# AirU_v2_0_wADC.net
KiCad netlist of a schematic drawn in EAGLE
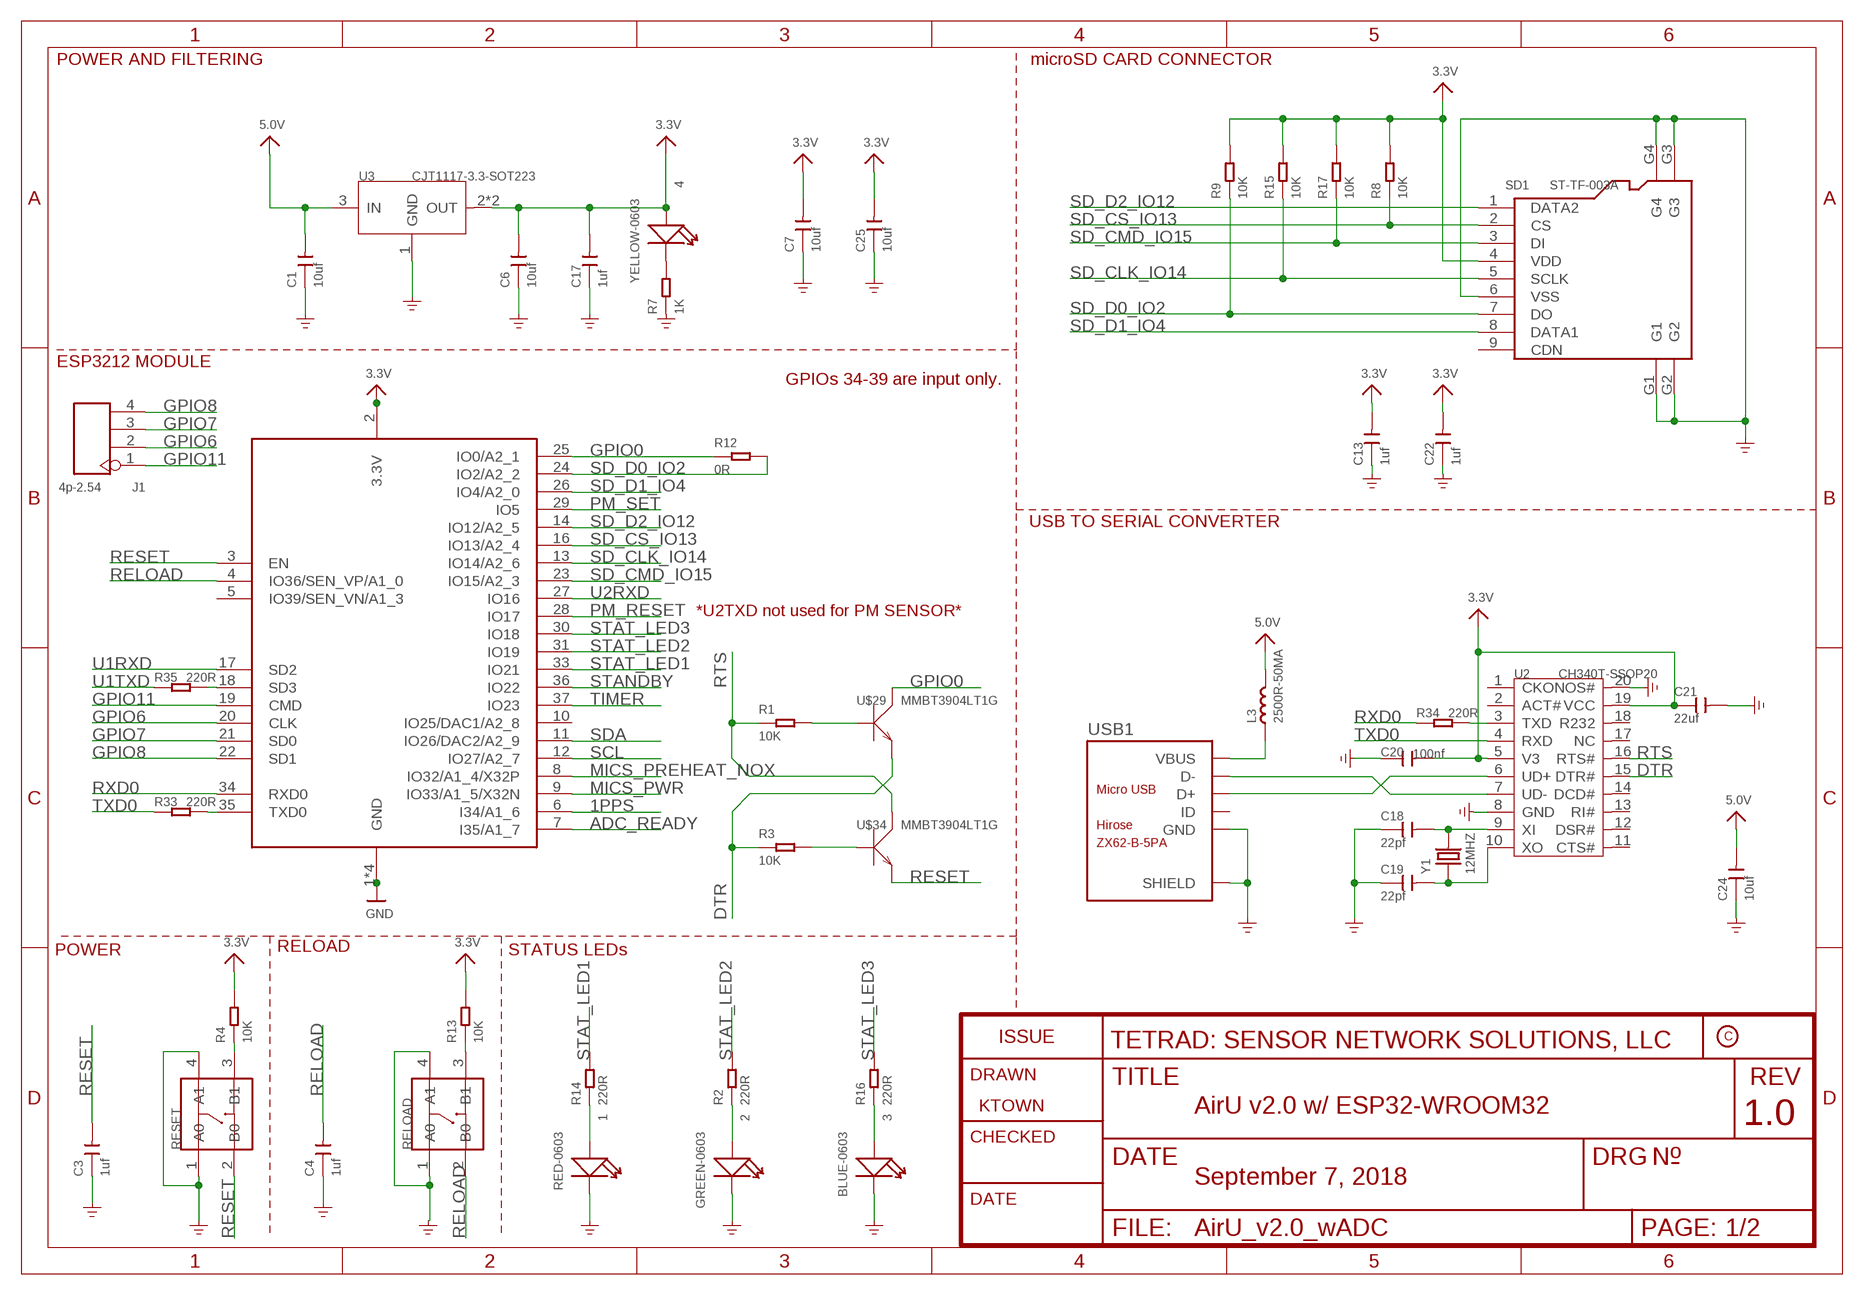
[diagram p0: schematic, sheet 1]
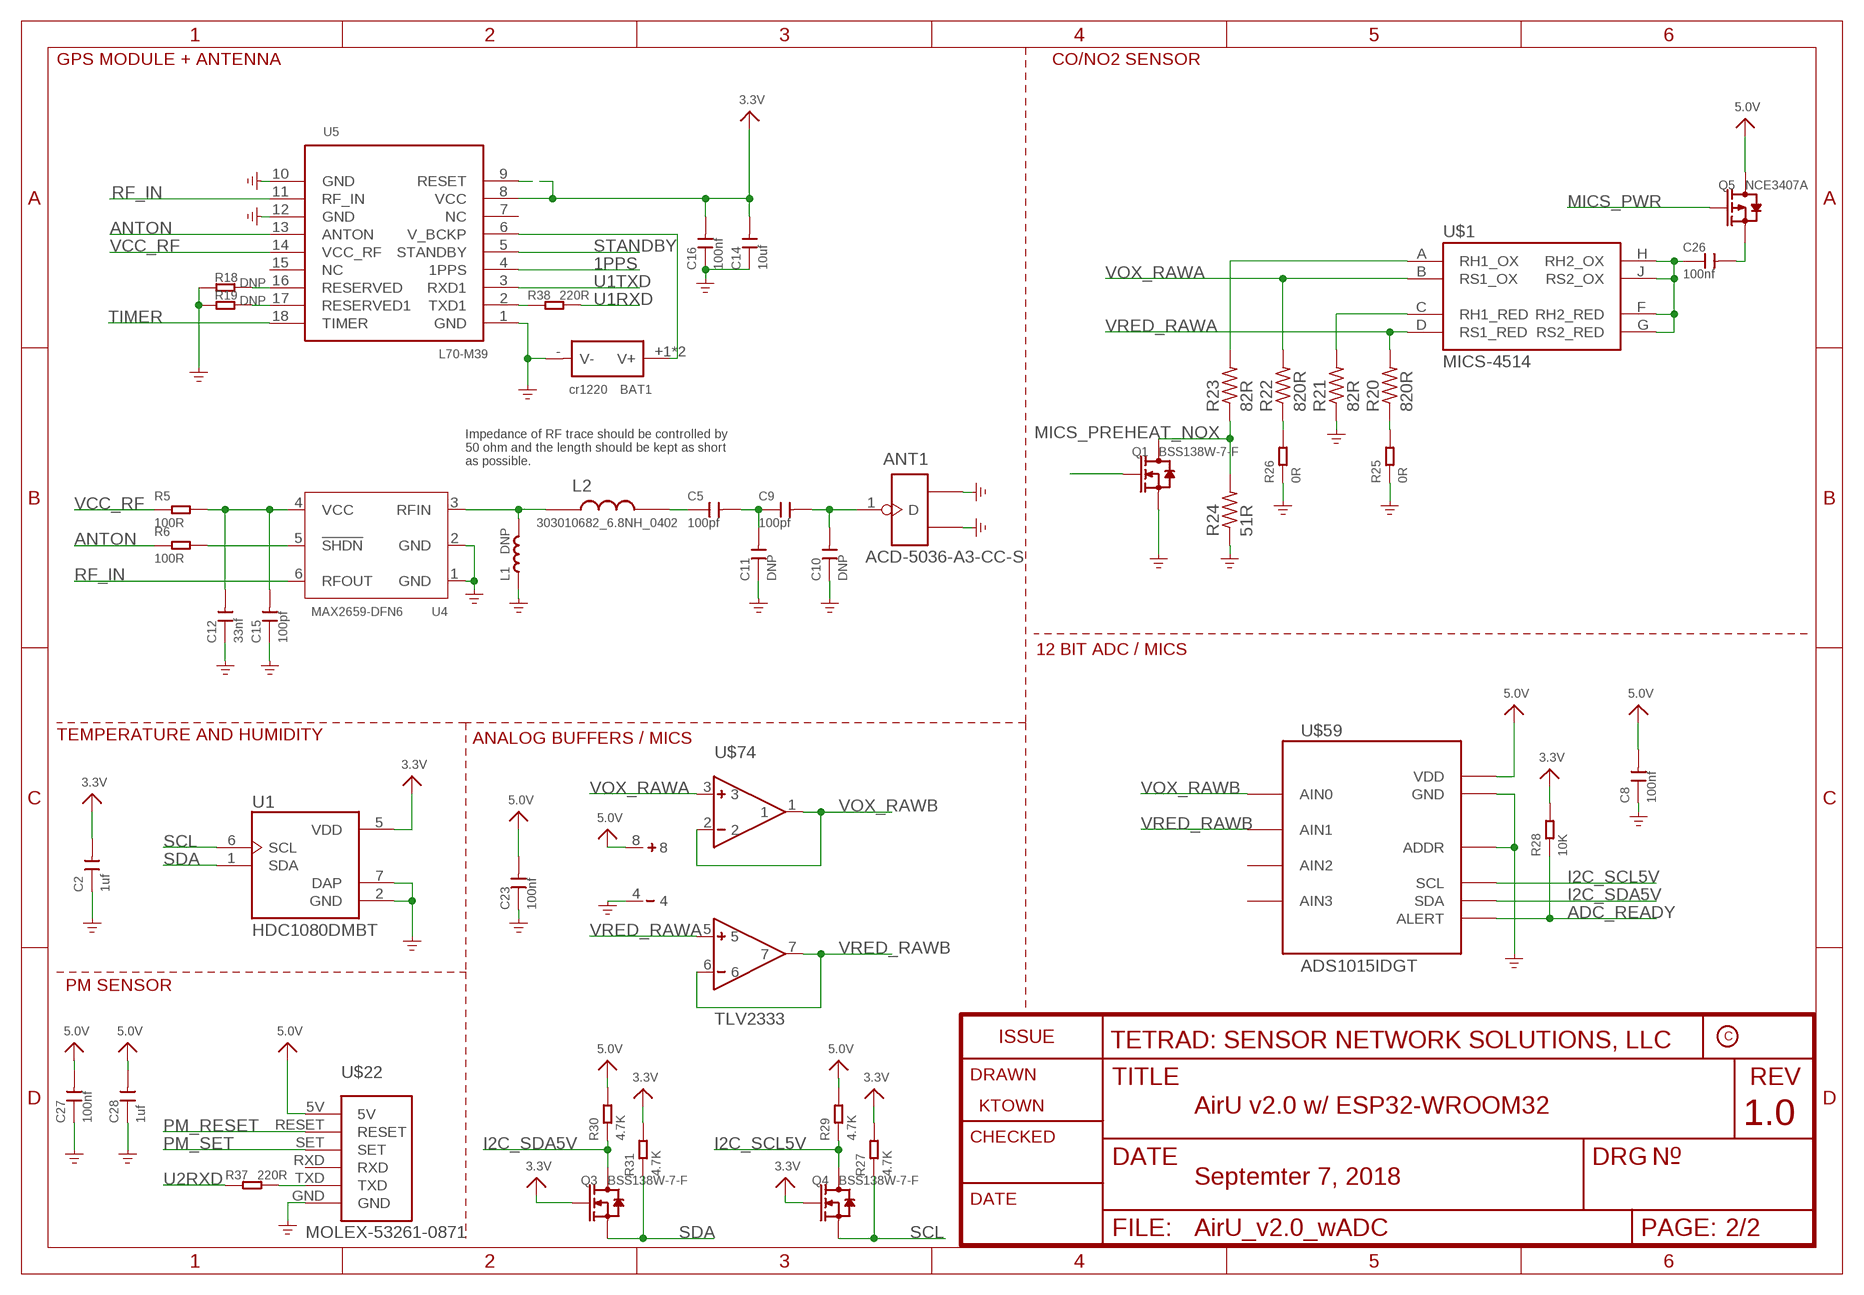
[diagram p1: schematic, sheet 2]

(export (version "E")
  (design (tool "Eeschema 10.0.6"))
  (components
    (comp (ref "1")
      (value "RED-0603")
      (footprint "eagle-import:LED-0603")
      (fields (field (name "MPN") "19-217-R6C-AL1M2VY-3T"))
      (libsource (lib "eagle-import") (part "LED-SMD-RED-DIFFUSED(0603)"))
    )
    (comp (ref "2")
      (value "GREEN-0603")
      (footprint "eagle-import:LED-0603")
      (fields (field (name "MPN") "19-217-G7C-AN1P2-3T"))
      (libsource (lib "eagle-import") (part "SMD-LED-CLEAR-GREEN(0603)"))
    )
    (comp (ref "3")
      (value "BLUE-0603")
      (footprint "eagle-import:LED-0603")
      (fields (field (name "MPN") "19-217-BHC-ZL1M2RY-3T"))
      (libsource (lib "eagle-import") (part "SMD-LED-CLEAR-BLUE(0603)"))
    )
    (comp (ref "4")
      (value "YELLOW-0603")
      (footprint "eagle-import:LED-0603")
      (fields (field (name "MPN") "19-217-Y5C-AM1N1VY-3T"))
      (libsource (lib "eagle-import") (part "SMD-LED-CLEAR-YELLOW(0603)"))
    )
    (comp (ref "C1")
      (value "10uf")
      (footprint "eagle-import:C0603")
      (fields (field (name "MPN") "CC0603KRX5R6BB106"))
      (libsource (lib "eagle-import") (part "CERAMIC-10UF-10V-10%-X5R(0603)"))
    )
    (comp (ref "C3")
      (value "1uf")
      (footprint "eagle-import:C0603")
      (fields (field (name "MPN") "CC0603KRX7R8BB105"))
      (libsource (lib "eagle-import") (part "CERAMIC-1UF-25V-10%-X7R(0603)"))
    )
    (comp (ref "C4")
      (value "1uf")
      (footprint "eagle-import:C0603")
      (fields (field (name "MPN") "CC0603KRX7R8BB105"))
      (libsource (lib "eagle-import") (part "CERAMIC-1UF-25V-10%-X7R(0603)"))
    )
    (comp (ref "C6")
      (value "10uf")
      (footprint "eagle-import:C0603")
      (fields (field (name "MPN") "CC0603KRX5R6BB106"))
      (libsource (lib "eagle-import") (part "CERAMIC-10UF-10V-10%-X5R(0603)"))
    )
    (comp (ref "C7")
      (value "10uf")
      (footprint "eagle-import:C0603")
      (fields (field (name "MPN") "CC0603KRX5R6BB106"))
      (libsource (lib "eagle-import") (part "CERAMIC-10UF-10V-10%-X5R(0603)"))
    )
    (comp (ref "C13")
      (value "1uf")
      (footprint "eagle-import:C0603")
      (fields (field (name "MPN") "CC0603KRX7R8BB105"))
      (libsource (lib "eagle-import") (part "CERAMIC-1UF-25V-10%-X7R(0603)"))
    )
    (comp (ref "C17")
      (value "1uf")
      (footprint "eagle-import:C0603")
      (fields (field (name "MPN") "CC0603KRX7R8BB105"))
      (libsource (lib "eagle-import") (part "CERAMIC-1UF-25V-10%-X7R(0603)"))
    )
    (comp (ref "C18")
      (value "22pf")
      (footprint "eagle-import:C0603")
      (fields (field (name "MPN") "CC0603JRNPO9BN220"))
      (libsource (lib "eagle-import") (part "CERAMIC-22PF-50V-5%-NPO(0603)"))
    )
    (comp (ref "C19")
      (value "22pf")
      (footprint "eagle-import:C0603")
      (fields (field (name "MPN") "CC0603JRNPO9BN220"))
      (libsource (lib "eagle-import") (part "CERAMIC-22PF-50V-5%-NPO(0603)"))
    )
    (comp (ref "C20")
      (value "100nf")
      (footprint "eagle-import:C0603")
      (fields (field (name "MPN") "CC0603KRX7R9BB104"))
      (libsource (lib "eagle-import") (part "CERAMIC-100NF-50V-10%-X7R(0603)"))
    )
    (comp (ref "C21")
      (value "22uf")
      (footprint "eagle-import:C0805")
      (fields (field (name "MPN") "CC0805MKX5R5BB226"))
      (libsource (lib "eagle-import") (part "CERAMIC-22UF-6.3V-20%-X5R(0805)"))
    )
    (comp (ref "C22")
      (value "1uf")
      (footprint "eagle-import:C0603")
      (fields (field (name "MPN") "CC0603KRX7R8BB105"))
      (libsource (lib "eagle-import") (part "CERAMIC-1UF-25V-10%-X7R(0603)"))
    )
    (comp (ref "C24")
      (value "10uf")
      (footprint "eagle-import:C0603")
      (fields (field (name "MPN") "CC0603KRX5R6BB106"))
      (libsource (lib "eagle-import") (part "CERAMIC-10UF-10V-10%-X5R(0603)"))
    )
    (comp (ref "C25")
      (value "10uf")
      (footprint "eagle-import:C0603")
      (fields (field (name "MPN") "CC0603KRX5R6BB106"))
      (libsource (lib "eagle-import") (part "CERAMIC-10UF-10V-10%-X5R(0603)"))
    )
    (comp (ref "J1")
      (value "4p-2.54")
      (footprint "eagle-import:H4-2.54")
      (fields (field (name "MPN") "P125-1104A0BS116A1"))
      (libsource (lib "eagle-import") (part "DIP-BLACK-MALE-HEADER-VERT(4P-2.54)"))
    )
    (comp (ref "L3")
      (value "2500R-50MA")
      (footprint "eagle-import:L0603")
      (libsource (lib "eagle-import") (part "SMD-FERRITE-BEAD-2500R-50MA(0603)"))
    )
    (comp (ref "R1")
      (value "10K")
      (footprint "eagle-import:R0603")
      (fields (field (name "MPN") "RC0603FR-0710KL"))
      (libsource (lib "eagle-import") (part "SMD-RES-10K-1%-1/10W(0603)"))
    )
    (comp (ref "R2")
      (value "220R")
      (footprint "eagle-import:R0603")
      (fields (field (name "MPN") "RC0603JR-07220RL"))
      (libsource (lib "eagle-import") (part "SMD-RES-220R-5%-1/10W(0603)"))
    )
    (comp (ref "R3")
      (value "10K")
      (footprint "eagle-import:R0603")
      (fields (field (name "MPN") "RC0603FR-0710KL"))
      (libsource (lib "eagle-import") (part "SMD-RES-10K-1%-1/10W(0603)"))
    )
    (comp (ref "R4")
      (value "10K")
      (footprint "eagle-import:R0603")
      (fields (field (name "MPN") "RC0603FR-0710KL"))
      (libsource (lib "eagle-import") (part "SMD-RES-10K-1%-1/10W(0603)"))
    )
    (comp (ref "R7")
      (value "1K")
      (footprint "eagle-import:R0603")
      (fields (field (name "MPN") "RC0603FR-071KL"))
      (libsource (lib "eagle-import") (part "SMD-RES-1K-1%-1/10W(0603)"))
    )
    (comp (ref "R8")
      (value "10K")
      (footprint "eagle-import:R0603")
      (fields (field (name "MPN") "RC0603FR-0710KL"))
      (libsource (lib "eagle-import") (part "SMD-RES-10K-1%-1/10W(0603)"))
    )
    (comp (ref "R9")
      (value "10K")
      (footprint "eagle-import:R0603")
      (fields (field (name "MPN") "RC0603FR-0710KL"))
      (libsource (lib "eagle-import") (part "SMD-RES-10K-1%-1/10W(0603)"))
    )
    (comp (ref "R12")
      (value "0R")
      (footprint "eagle-import:R0603")
      (fields (field (name "MPN") "RC0603JR-070RL"))
      (libsource (lib "eagle-import") (part "SMD-RES-0R-5%-1/10W(0603)"))
    )
    (comp (ref "R13")
      (value "10K")
      (footprint "eagle-import:R0603")
      (fields (field (name "MPN") "RC0603FR-0710KL"))
      (libsource (lib "eagle-import") (part "SMD-RES-10K-1%-1/10W(0603)"))
    )
    (comp (ref "R14")
      (value "220R")
      (footprint "eagle-import:R0603")
      (fields (field (name "MPN") "RC0603JR-07220RL"))
      (libsource (lib "eagle-import") (part "SMD-RES-220R-5%-1/10W(0603)"))
    )
    (comp (ref "R15")
      (value "10K")
      (footprint "eagle-import:R0603")
      (fields (field (name "MPN") "RC0603FR-0710KL"))
      (libsource (lib "eagle-import") (part "SMD-RES-10K-1%-1/10W(0603)"))
    )
    (comp (ref "R16")
      (value "220R")
      (footprint "eagle-import:R0603")
      (fields (field (name "MPN") "RC0603JR-07220RL"))
      (libsource (lib "eagle-import") (part "SMD-RES-220R-5%-1/10W(0603)"))
    )
    (comp (ref "R17")
      (value "10K")
      (footprint "eagle-import:R0603")
      (fields (field (name "MPN") "RC0603FR-0710KL"))
      (libsource (lib "eagle-import") (part "SMD-RES-10K-1%-1/10W(0603)"))
    )
    (comp (ref "R33")
      (value "220R")
      (footprint "eagle-import:R0603")
      (fields (field (name "MPN") "RC0603JR-07220RL"))
      (libsource (lib "eagle-import") (part "SMD-RES-220R-5%-1/10W(0603)"))
    )
    (comp (ref "R34")
      (value "220R")
      (footprint "eagle-import:R0603")
      (fields (field (name "MPN") "RC0603JR-07220RL"))
      (libsource (lib "eagle-import") (part "SMD-RES-220R-5%-1/10W(0603)"))
    )
    (comp (ref "R35")
      (value "220R")
      (footprint "eagle-import:R0603")
      (fields (field (name "MPN") "RC0603JR-07220RL"))
      (libsource (lib "eagle-import") (part "SMD-RES-220R-5%-1/10W(0603)"))
    )
    (comp (ref "RELOAD")
      (value "DIP-SWITCH-TACTILE-SPST-NO/TS-1109(4P-D6.0MM)'TS-1109'")
      (footprint "eagle-import:SW4-6.0X6.0X5.0MM")
      (libsource (lib "eagle-import") (part "DIP-SWITCH-TACTILE-SPST-NO/TS-1109(4P-D6.0MM)'TS-1109'"))
    )
    (comp (ref "RESET")
      (value "DIP-SWITCH-TACTILE-SPST-NO/TS-1109(4P-D6.0MM)'TS-1109'")
      (footprint "eagle-import:SW4-6.0X6.0X5.0MM")
      (libsource (lib "eagle-import") (part "DIP-SWITCH-TACTILE-SPST-NO/TS-1109(4P-D6.0MM)'TS-1109'"))
    )
    (comp (ref "SD1")
      (value "ST-TF-003A")
      (footprint "eagle-import:MICRO-SD9+4P-SMD-16.1X14.5X1.85MM")
      (libsource (lib "eagle-import") (part "MICRO-SD-CARD-SOCKET-9P(ST-TF-003A)"))
    )
    (comp (ref "U$29")
      (value "MMBT3904LT1G")
      (footprint "eagle-import:SOT-23")
      (libsource (lib "eagle-import") (part "SMD-TRANSISTORS-NPN-40V-200MA-MMBT3904LT1G(SOT-23)"))
    )
    (comp (ref "U$34")
      (value "MMBT3904LT1G")
      (footprint "eagle-import:SOT-23")
      (libsource (lib "eagle-import") (part "SMD-TRANSISTORS-NPN-40V-200MA-MMBT3904LT1G(SOT-23)"))
    )
    (comp (ref "U2")
      (value "CH340T-SSOP20")
      (footprint "eagle-import:SSOP20-0.65-7.6X5.2MM")
      (fields (field (name "MPN") "CH340T"))
      (libsource (lib "eagle-import") (part "INTERFACE-CH340T(SSOP20)"))
    )
    (comp (ref "U3")
      (value "CJT1117-3.3-SOT223")
      (footprint "eagle-import:SOT-223")
      (fields (field (name "MPN") "CJT1117-3.3"))
      (libsource (lib "eagle-import") (part "PMIC-CJT1117-3.3(SOT223)"))
    )
    (comp (ref "USB1")
      (value "ZX62-B-5PA")
      (footprint "eagle-import:MICRO-USB5+6P-SMD-0.65-AB")
      (libsource (lib "eagle-import") (part "MICRO-USB-SMD(ZX62-B-5PA)"))
    )
    (comp (ref "X2")
      (value "ESP32_WROOM32_SKINNY")
      (footprint "eagle-import:WROOM32_SKINNY")
      (libsource (lib "eagle-import") (part "ESP32_WROOM32_SKINNY"))
    )
    (comp (ref "Y1")
      (value "12MHZ")
      (footprint "eagle-import:X2-SMD-5.0X3.2X1.3MM")
      (fields (field (name "MPN") "5032/2P"))
      (libsource (lib "eagle-import") (part "SMD-CRYSTAL-12MHZ-20PF-20PPM-40R(2P-5.0X3.2MM)"))
    )
    (comp (ref "ANT1")
      (value "ACD-5036-A3-CC-S")
      (footprint "eagle-import:ANT3-SMD-5.2X3.7X0.7MM")
      (libsource (lib "eagle-import") (part "ANTENNA-ACD5036"))
    )
    (comp (ref "BAT1")
      (value "cr1220")
      (footprint "eagle-import:BAT2P-13.5-CR1220")
      (libsource (lib "eagle-import") (part "DIP-BATTERY-CELL-HOLDER(1220)"))
    )
    (comp (ref "C2")
      (value "1uf")
      (footprint "eagle-import:C0603")
      (fields (field (name "MPN") "CC0603KRX7R8BB105"))
      (libsource (lib "eagle-import") (part "CERAMIC-1UF-25V-10%-X7R(0603)"))
    )
    (comp (ref "C5")
      (value "100pf")
      (footprint "eagle-import:C0603")
      (fields (field (name "MPN") "CC0603JRNPO9BN101"))
      (libsource (lib "eagle-import") (part "CERAMIC-100PF-50V-5%-NPO(0603)"))
    )
    (comp (ref "C8")
      (value "100nf")
      (footprint "eagle-import:C0603")
      (fields (field (name "MPN") "CC0603KRX7R9BB104"))
      (libsource (lib "eagle-import") (part "CERAMIC-100NF-50V-10%-X7R(0603)"))
    )
    (comp (ref "C9")
      (value "100pf")
      (footprint "eagle-import:C0603")
      (fields (field (name "MPN") "CC0603JRNPO9BN101"))
      (libsource (lib "eagle-import") (part "CERAMIC-100PF-50V-5%-NPO(0603)"))
    )
    (comp (ref "C10")
      (value "DNP")
      (footprint "eagle-import:C0603")
      (fields (field (name "MPN") "CC0603JRNPO9BN101"))
      (libsource (lib "eagle-import") (part "CERAMIC-100PF-50V-5%-NPO(0603)"))
    )
    (comp (ref "C11")
      (value "DNP")
      (footprint "eagle-import:C0603")
      (fields (field (name "MPN") "CC0603JRNPO9BN101"))
      (libsource (lib "eagle-import") (part "CERAMIC-100PF-50V-5%-NPO(0603)"))
    )
    (comp (ref "C12")
      (value "33nf")
      (footprint "eagle-import:C0603")
      (fields (field (name "MPN") "CC0603KRX7R9BB333"))
      (libsource (lib "eagle-import") (part "CERAMIC-33NF-50V-10%-X7R(0603)"))
    )
    (comp (ref "C14")
      (value "10uf")
      (footprint "eagle-import:C0603")
      (fields (field (name "MPN") "CC0603KRX5R6BB106"))
      (libsource (lib "eagle-import") (part "CERAMIC-10UF-10V-10%-X5R(0603)"))
    )
    (comp (ref "C15")
      (value "100pf")
      (footprint "eagle-import:C0603")
      (fields (field (name "MPN") "CC0603JRNPO9BN101"))
      (libsource (lib "eagle-import") (part "CERAMIC-100PF-50V-5%-NPO(0603)"))
    )
    (comp (ref "C16")
      (value "100nf")
      (footprint "eagle-import:C0603")
      (fields (field (name "MPN") "CC0603KRX7R9BB104"))
      (libsource (lib "eagle-import") (part "CERAMIC-100NF-50V-10%-X7R(0603)"))
    )
    (comp (ref "C23")
      (value "100nf")
      (footprint "eagle-import:C0603")
      (fields (field (name "MPN") "CC0603KRX7R9BB104"))
      (libsource (lib "eagle-import") (part "CERAMIC-100NF-50V-10%-X7R(0603)"))
    )
    (comp (ref "C26")
      (value "100nf")
      (footprint "eagle-import:C0603")
      (fields (field (name "MPN") "CC0603KRX7R9BB104"))
      (libsource (lib "eagle-import") (part "CERAMIC-100NF-50V-10%-X7R(0603)"))
    )
    (comp (ref "C27")
      (value "100nf")
      (footprint "eagle-import:C0603")
      (fields (field (name "MPN") "CC0603KRX7R9BB104"))
      (libsource (lib "eagle-import") (part "CERAMIC-100NF-50V-10%-X7R(0603)"))
    )
    (comp (ref "C28")
      (value "1uf")
      (footprint "eagle-import:C0603")
      (fields (field (name "MPN") "CC0603KRX7R8BB105"))
      (libsource (lib "eagle-import") (part "CERAMIC-1UF-25V-10%-X7R(0603)"))
    )
    (comp (ref "L1")
      (value "DNP")
      (footprint "eagle-import:L0201")
      (libsource (lib "eagle-import") (part "INDUCTOR/FERRITE-BEAD-0201"))
    )
    (comp (ref "L2")
      (value "303010682_6.8NH_0402")
      (footprint "eagle-import:L0402")
      (libsource (lib "eagle-import") (part "303010682_6.8NH_0402"))
    )
    (comp (ref "Q1")
      (value "BSS138W-7-F")
      (footprint "eagle-import:SOT-23")
      (libsource (lib "eagle-import") (part "SMD-MOSFET-N-CH-50V-200MA-BSS138W-7-F(SOT-23)"))
    )
    (comp (ref "Q3")
      (value "BSS138W-7-F")
      (footprint "eagle-import:SOT-23")
      (libsource (lib "eagle-import") (part "SMD-MOSFET-N-CH-50V-200MA-BSS138W-7-F(SOT-23)"))
    )
    (comp (ref "Q4")
      (value "BSS138W-7-F")
      (footprint "eagle-import:SOT-23")
      (libsource (lib "eagle-import") (part "SMD-MOSFET-N-CH-50V-200MA-BSS138W-7-F(SOT-23)"))
    )
    (comp (ref "Q5")
      (value "NCE3407A")
      (footprint "eagle-import:SOT-23")
      (libsource (lib "eagle-import") (part "SMD-MOSFET-P-CH-VDC=30V-ID=4.3A-NCE3407A(SOT-23)"))
    )
    (comp (ref "R5")
      (value "100R")
      (footprint "eagle-import:R0603")
      (fields (field (name "MPN") "RC0603JR-07100RL"))
      (libsource (lib "eagle-import") (part "SMD-RES-100R-5%-1/10W(0603)"))
    )
    (comp (ref "R6")
      (value "100R")
      (footprint "eagle-import:R0603")
      (fields (field (name "MPN") "RC0603JR-07100RL"))
      (libsource (lib "eagle-import") (part "SMD-RES-100R-5%-1/10W(0603)"))
    )
    (comp (ref "R18")
      (value "DNP")
      (footprint "eagle-import:R0603")
      (fields (field (name "MPN") "RC0603FR-0710KL"))
      (libsource (lib "eagle-import") (part "SMD-RES-10K-1%-1/10W(0603)"))
    )
    (comp (ref "R19")
      (value "DNP")
      (footprint "eagle-import:R0603")
      (fields (field (name "MPN") "RC0603FR-0710KL"))
      (libsource (lib "eagle-import") (part "SMD-RES-10K-1%-1/10W(0603)"))
    )
    (comp (ref "R20")
      (value "820R")
      (footprint "eagle-import:R0805")
      (libsource (lib "eagle-import") (part "R-US_R0805"))
    )
    (comp (ref "R21")
      (value "82R")
      (footprint "eagle-import:R0603")
      (libsource (lib "eagle-import") (part "R-US_R0603"))
    )
    (comp (ref "R22")
      (value "820R")
      (footprint "eagle-import:R0805")
      (libsource (lib "eagle-import") (part "R-US_R0805"))
    )
    (comp (ref "R23")
      (value "82R")
      (footprint "eagle-import:R0603")
      (libsource (lib "eagle-import") (part "R-US_R0603"))
    )
    (comp (ref "R24")
      (value "51R")
      (footprint "eagle-import:R0603")
      (libsource (lib "eagle-import") (part "R-US_R0603"))
    )
    (comp (ref "R25")
      (value "0R")
      (footprint "eagle-import:R0603")
      (fields (field (name "MPN") "RC0603JR-070RL"))
      (libsource (lib "eagle-import") (part "SMD-RES-0R-5%-1/10W(0603)"))
    )
    (comp (ref "R26")
      (value "0R")
      (footprint "eagle-import:R0603")
      (fields (field (name "MPN") "RC0603JR-070RL"))
      (libsource (lib "eagle-import") (part "SMD-RES-0R-5%-1/10W(0603)"))
    )
    (comp (ref "R27")
      (value "4.7K")
      (footprint "eagle-import:R0603")
      (fields (field (name "MPN") "RC0603JR-074K7L"))
      (libsource (lib "eagle-import") (part "SMD-RES-4.7K-5%-1/10W(0603)"))
    )
    (comp (ref "R28")
      (value "10K")
      (footprint "eagle-import:R0603")
      (fields (field (name "MPN") "RC0603FR-0710KL"))
      (libsource (lib "eagle-import") (part "SMD-RES-10K-1%-1/10W(0603)"))
    )
    (comp (ref "R29")
      (value "4.7K")
      (footprint "eagle-import:R0603")
      (fields (field (name "MPN") "RC0603JR-074K7L"))
      (libsource (lib "eagle-import") (part "SMD-RES-4.7K-5%-1/10W(0603)"))
    )
    (comp (ref "R30")
      (value "4.7K")
      (footprint "eagle-import:R0603")
      (fields (field (name "MPN") "RC0603JR-074K7L"))
      (libsource (lib "eagle-import") (part "SMD-RES-4.7K-5%-1/10W(0603)"))
    )
    (comp (ref "R31")
      (value "4.7K")
      (footprint "eagle-import:R0603")
      (fields (field (name "MPN") "RC0603JR-074K7L"))
      (libsource (lib "eagle-import") (part "SMD-RES-4.7K-5%-1/10W(0603)"))
    )
    (comp (ref "R37")
      (value "220R")
      (footprint "eagle-import:R0603")
      (fields (field (name "MPN") "RC0603JR-07220RL"))
      (libsource (lib "eagle-import") (part "SMD-RES-220R-5%-1/10W(0603)"))
    )
    (comp (ref "R38")
      (value "220R")
      (footprint "eagle-import:R0603")
      (fields (field (name "MPN") "RC0603JR-07220RL"))
      (libsource (lib "eagle-import") (part "SMD-RES-220R-5%-1/10W(0603)"))
    )
    (comp (ref "U$1")
      (value "MICS-4514")
      (footprint "eagle-import:MICS_10-SMD")
      (fields (field (name "MF") "Amphenol"))
      (libsource (lib "eagle-import") (part "MICS-4514"))
    )
    (comp (ref "U$22")
      (value "MOLEX-53261-0871")
      (footprint "eagle-import:MOLEX-53261-0871")
      (libsource (lib "eagle-import") (part "MOLEX-53261-0871"))
    )
    (comp (ref "U$59")
      (value "ADS1015IDGT")
      (footprint "eagle-import:MSOP10_0.5")
      (fields (field (name "MF") "Texas Instruments") (field (name "MP") "ADS1015"))
      (libsource (lib "eagle-import") (part "ADS1015IDGT"))
    )
    (comp (ref "U$74")
      (value "TLV2333")
      (footprint "eagle-import:TLV2333")
      (libsource (lib "eagle-import") (part "TLV2333"))
    )
    (comp (ref "U1")
      (value "HDC1080DMBT")
      (footprint "eagle-import:SON100P300X300X80-7N")
      (fields (field (name "DIGI-KEY_PART_NUMBER") "296-43864-1-ND") (field (name "MF") "Texas Instruments"))
      (libsource (lib "eagle-import") (part "HDC1080DMBT"))
    )
    (comp (ref "U4")
      (value "MAX2659-DFN6")
      (footprint "eagle-import:DFN6-0.5-1.5X1.2X0.72MM")
      (fields (field (name "MPN") "MAX2659"))
      (libsource (lib "eagle-import") (part "AMPLIFIER-MAX2659"))
    )
    (comp (ref "U5")
      (value "L70-M39")
      (footprint "eagle-import:LGA18-1.1-9.7X10.1X2.5MM")
      (fields (field (name "MPN") "L70"))
      (libsource (lib "eagle-import") (part "MOUDLE-GPS-L70-HARDWARE"))
    )
  )
  (nets
    (net (code "1") (name "1PPS") (class "Default")
      (node (ref "U5") (pin "4") (pinfunction "1PPS_4") (pintype "bidirectional"))
      (node (ref "X2") (pin "6") (pinfunction "I34/A1_6_6") (pintype "bidirectional"))
    )
    (net (code "2") (name "3.3V") (class "Default")
      (node (ref "4") (pin "+") (pinfunction "+_+") (pintype "passive"))
      (node (ref "C13") (pin "2") (pinfunction "2_2") (pintype "passive"))
      (node (ref "C14") (pin "2") (pinfunction "2_2") (pintype "passive"))
      (node (ref "C16") (pin "2") (pinfunction "2_2") (pintype "passive"))
      (node (ref "C17") (pin "2") (pinfunction "2_2") (pintype "passive"))
      (node (ref "C2") (pin "2") (pinfunction "2_2") (pintype "passive"))
      (node (ref "C20") (pin "2") (pinfunction "2_2") (pintype "passive"))
      (node (ref "C21") (pin "1") (pinfunction "1_1") (pintype "passive"))
      (node (ref "C22") (pin "2") (pinfunction "2_2") (pintype "passive"))
      (node (ref "C25") (pin "2") (pinfunction "2_2") (pintype "passive"))
      (node (ref "C6") (pin "2") (pinfunction "2_2") (pintype "passive"))
      (node (ref "C7") (pin "2") (pinfunction "2_2") (pintype "passive"))
      (node (ref "Q3") (pin "1") (pinfunction "G_1") (pintype "passive"))
      (node (ref "Q4") (pin "1") (pinfunction "G_1") (pintype "passive"))
      (node (ref "R13") (pin "2") (pinfunction "2_2") (pintype "passive"))
      (node (ref "R15") (pin "2") (pinfunction "2_2") (pintype "passive"))
      (node (ref "R17") (pin "2") (pinfunction "2_2") (pintype "passive"))
      (node (ref "R27") (pin "2") (pinfunction "2_2") (pintype "passive"))
      (node (ref "R28") (pin "2") (pinfunction "2_2") (pintype "passive"))
      (node (ref "R31") (pin "2") (pinfunction "2_2") (pintype "passive"))
      (node (ref "R4") (pin "2") (pinfunction "2_2") (pintype "passive"))
      (node (ref "R8") (pin "2") (pinfunction "2_2") (pintype "passive"))
      (node (ref "R9") (pin "2") (pinfunction "2_2") (pintype "passive"))
      (node (ref "SD1") (pin "4") (pinfunction "VDD_4") (pintype "bidirectional"))
      (node (ref "U1") (pin "5") (pinfunction "VDD_5") (pintype "power_in"))
      (node (ref "U2") (pin "19") (pinfunction "VCC_19") (pintype "power_in"))
      (node (ref "U2") (pin "5") (pinfunction "V3_5") (pintype "power_in"))
      (node (ref "U3") (pin "2") (pinfunction "OUT_2") (pintype "bidirectional"))
      (node (ref "U3") (pin "TER") (pinfunction "OUT_TER") (pintype "bidirectional"))
      (node (ref "U5") (pin "8") (pinfunction "VCC_8") (pintype "power_in"))
      (node (ref "U5") (pin "9") (pinfunction "RESET_9") (pintype "bidirectional"))
      (node (ref "X2") (pin "2") (pinfunction "3.3V_2") (pintype "passive"))
    )
    (net (code "3") (name "5.0V") (class "Default")
      (node (ref "C1") (pin "2") (pinfunction "2_2") (pintype "passive"))
      (node (ref "C23") (pin "2") (pinfunction "2_2") (pintype "passive"))
      (node (ref "C24") (pin "2") (pinfunction "2_2") (pintype "passive"))
      (node (ref "C27") (pin "2") (pinfunction "2_2") (pintype "passive"))
      (node (ref "C28") (pin "2") (pinfunction "2_2") (pintype "passive"))
      (node (ref "C8") (pin "2") (pinfunction "2_2") (pintype "passive"))
      (node (ref "L3") (pin "2") (pinfunction "2_2") (pintype "passive"))
      (node (ref "Q5") (pin "3") (pinfunction "D_3") (pintype "passive"))
      (node (ref "R29") (pin "2") (pinfunction "2_2") (pintype "passive"))
      (node (ref "R30") (pin "2") (pinfunction "2_2") (pintype "passive"))
      (node (ref "U$22") (pin "5V") (pinfunction "5V_5V") (pintype "bidirectional"))
      (node (ref "U$59") (pin "8") (pinfunction "VDD_8") (pintype "power_in"))
      (node (ref "U$74") (pin "8") (pinfunction "8_8") (pintype "bidirectional"))
      (node (ref "U3") (pin "3") (pinfunction "IN_3") (pintype "bidirectional"))
    )
    (net (code "4") (name "ADC_READY") (class "Default")
      (node (ref "R28") (pin "1") (pinfunction "1_1") (pintype "passive"))
      (node (ref "U$59") (pin "2") (pinfunction "ALERT_2") (pintype "output"))
      (node (ref "X2") (pin "7") (pinfunction "I35/A1_7_7") (pintype "bidirectional"))
    )
    (net (code "5") (name "ANTON") (class "Default")
      (node (ref "R6") (pin "1") (pinfunction "1_1") (pintype "passive"))
      (node (ref "U5") (pin "13") (pinfunction "ANTON_13") (pintype "bidirectional"))
    )
    (net (code "6") (name "DTR") (class "Default")
      (node (ref "R3") (pin "1") (pinfunction "1_1") (pintype "passive"))
      (node (ref "U$29") (pin "2") (pinfunction "E_2") (pintype "passive"))
      (node (ref "U2") (pin "15") (pinfunction "DTR#_15") (pintype "output"))
    )
    (net (code "7") (name "GND") (class "Default")
      (node (ref "1") (pin "-") (pinfunction "-_-") (pintype "passive"))
      (node (ref "2") (pin "-") (pinfunction "-_-") (pintype "passive"))
      (node (ref "3") (pin "-") (pinfunction "-_-") (pintype "passive"))
      (node (ref "ANT1") (pin "2") (pinfunction "GND1_2") (pintype "bidirectional"))
      (node (ref "ANT1") (pin "3") (pinfunction "GND2_3") (pintype "bidirectional"))
      (node (ref "BAT1") (pin "-") (pinfunction "V-_-") (pintype "bidirectional"))
      (node (ref "C1") (pin "1") (pinfunction "1_1") (pintype "passive"))
      (node (ref "C10") (pin "1") (pinfunction "1_1") (pintype "passive"))
      (node (ref "C11") (pin "1") (pinfunction "1_1") (pintype "passive"))
      (node (ref "C12") (pin "1") (pinfunction "1_1") (pintype "passive"))
      (node (ref "C13") (pin "1") (pinfunction "1_1") (pintype "passive"))
      (node (ref "C14") (pin "1") (pinfunction "1_1") (pintype "passive"))
      (node (ref "C15") (pin "1") (pinfunction "1_1") (pintype "passive"))
      (node (ref "C16") (pin "1") (pinfunction "1_1") (pintype "passive"))
      (node (ref "C17") (pin "1") (pinfunction "1_1") (pintype "passive"))
      (node (ref "C18") (pin "1") (pinfunction "1_1") (pintype "passive"))
      (node (ref "C19") (pin "1") (pinfunction "1_1") (pintype "passive"))
      (node (ref "C2") (pin "1") (pinfunction "1_1") (pintype "passive"))
      (node (ref "C20") (pin "1") (pinfunction "1_1") (pintype "passive"))
      (node (ref "C21") (pin "2") (pinfunction "2_2") (pintype "passive"))
      (node (ref "C22") (pin "1") (pinfunction "1_1") (pintype "passive"))
      (node (ref "C23") (pin "1") (pinfunction "1_1") (pintype "passive"))
      (node (ref "C24") (pin "1") (pinfunction "1_1") (pintype "passive"))
      (node (ref "C25") (pin "1") (pinfunction "1_1") (pintype "passive"))
      (node (ref "C27") (pin "1") (pinfunction "1_1") (pintype "passive"))
      (node (ref "C28") (pin "1") (pinfunction "1_1") (pintype "passive"))
      (node (ref "C3") (pin "1") (pinfunction "1_1") (pintype "passive"))
      (node (ref "C4") (pin "1") (pinfunction "1_1") (pintype "passive"))
      (node (ref "C6") (pin "1") (pinfunction "1_1") (pintype "passive"))
      (node (ref "C7") (pin "1") (pinfunction "1_1") (pintype "passive"))
      (node (ref "C8") (pin "1") (pinfunction "1_1") (pintype "passive"))
      (node (ref "L1") (pin "1") (pinfunction "1_1") (pintype "passive"))
      (node (ref "Q1") (pin "2") (pinfunction "S_2") (pintype "passive"))
      (node (ref "R18") (pin "1") (pinfunction "1_1") (pintype "passive"))
      (node (ref "R19") (pin "1") (pinfunction "1_1") (pintype "passive"))
      (node (ref "R21") (pin "1") (pinfunction "1_1") (pintype "passive"))
      (node (ref "R24") (pin "1") (pinfunction "1_1") (pintype "passive"))
      (node (ref "R25") (pin "1") (pinfunction "1_1") (pintype "passive"))
      (node (ref "R26") (pin "1") (pinfunction "1_1") (pintype "passive"))
      (node (ref "R7") (pin "1") (pinfunction "1_1") (pintype "passive"))
      (node (ref "RELOAD") (pin "1") (pinfunction "A0_1") (pintype "bidirectional"))
      (node (ref "RELOAD") (pin "4") (pinfunction "A1_4") (pintype "bidirectional"))
      (node (ref "RESET") (pin "1") (pinfunction "A0_1") (pintype "bidirectional"))
      (node (ref "RESET") (pin "4") (pinfunction "A1_4") (pintype "bidirectional"))
      (node (ref "SD1") (pin "6") (pinfunction "VSS_6") (pintype "bidirectional"))
      (node (ref "SD1") (pin "G1") (pinfunction "G1_G1") (pintype "bidirectional"))
      (node (ref "SD1") (pin "G2") (pinfunction "G2_G2") (pintype "bidirectional"))
      (node (ref "SD1") (pin "G3") (pinfunction "G3_G3") (pintype "bidirectional"))
      (node (ref "SD1") (pin "G4") (pinfunction "G4_G4") (pintype "bidirectional"))
      (node (ref "U$22") (pin "GND") (pinfunction "GND_GND") (pintype "bidirectional"))
      (node (ref "U$59") (pin "1") (pinfunction "ADDR_1") (pintype "input"))
      (node (ref "U$59") (pin "3") (pinfunction "GND_3") (pintype "power_in"))
      (node (ref "U$74") (pin "4") (pinfunction "4_4") (pintype "bidirectional"))
      (node (ref "U1") (pin "2") (pinfunction "GND_2") (pintype "power_in"))
      (node (ref "U1") (pin "7") (pinfunction "DAP_7") (pintype "power_in"))
      (node (ref "U2") (pin "20") (pinfunction "NOS#_20") (pintype "power_in"))
      (node (ref "U2") (pin "8") (pinfunction "GND_8") (pintype "power_in"))
      (node (ref "U3") (pin "1") (pinfunction "GND_1") (pintype "bidirectional"))
      (node (ref "U4") (pin "1") (pinfunction "GND_1") (pintype "power_in"))
      (node (ref "U4") (pin "2") (pinfunction "GND_2") (pintype "power_in"))
      (node (ref "U5") (pin "1") (pinfunction "GND_1") (pintype "power_in"))
      (node (ref "U5") (pin "10") (pinfunction "GND_10") (pintype "power_in"))
      (node (ref "U5") (pin "12") (pinfunction "GND_12") (pintype "bidirectional"))
      (node (ref "USB1") (pin "5") (pinfunction "GND_5") (pintype "power_in"))
      (node (ref "USB1") (pin "P1") (pinfunction "SHIELD_P1") (pintype "power_in"))
      (node (ref "USB1") (pin "P2") (pinfunction "SHIELD_P2") (pintype "power_in"))
      (node (ref "USB1") (pin "P3_1") (pinfunction "SHIELD_P3_1") (pintype "power_in"))
      (node (ref "USB1") (pin "P3_2") (pinfunction "SHIELD_P3_2") (pintype "power_in"))
      (node (ref "USB1") (pin "P3_3") (pinfunction "SHIELD_P3_3") (pintype "power_in"))
      (node (ref "USB1") (pin "P4_1") (pinfunction "SHIELD_P4_1") (pintype "power_in"))
      (node (ref "USB1") (pin "P4_2") (pinfunction "SHIELD_P4_2") (pintype "power_in"))
      (node (ref "USB1") (pin "P4_3") (pinfunction "SHIELD_P4_3") (pintype "power_in"))
      (node (ref "USB1") (pin "P5") (pinfunction "SHIELD_P5") (pintype "power_in"))
      (node (ref "USB1") (pin "P6") (pinfunction "SHIELD_P6") (pintype "power_in"))
      (node (ref "X2") (pin "1") (pinfunction "GND_1") (pintype "passive"))
      (node (ref "X2") (pin "15") (pinfunction "GND_15") (pintype "passive"))
      (node (ref "X2") (pin "38") (pinfunction "GND_38") (pintype "passive"))
      (node (ref "X2") (pin "P$1") (pinfunction "GND_P$1") (pintype "passive"))
    )
    (net (code "8") (name "GPIO0") (class "Default")
      (node (ref "R12") (pin "1") (pinfunction "1_1") (pintype "passive"))
      (node (ref "U$29") (pin "3") (pinfunction "C_3") (pintype "passive"))
      (node (ref "X2") (pin "25") (pinfunction "IO0/A2_1_25") (pintype "bidirectional"))
    )
    (net (code "9") (name "GPIO6") (class "Default")
      (node (ref "J1") (pin "2") (pinfunction "P$2_2") (pintype "bidirectional"))
      (node (ref "X2") (pin "20") (pinfunction "CLK_20") (pintype "bidirectional"))
    )
    (net (code "10") (name "GPIO7") (class "Default")
      (node (ref "J1") (pin "3") (pinfunction "P$3_3") (pintype "bidirectional"))
      (node (ref "X2") (pin "21") (pinfunction "SD0_21") (pintype "bidirectional"))
    )
    (net (code "11") (name "GPIO8") (class "Default")
      (node (ref "J1") (pin "4") (pinfunction "P$4_4") (pintype "bidirectional"))
      (node (ref "X2") (pin "22") (pinfunction "SD1_22") (pintype "bidirectional"))
    )
    (net (code "12") (name "GPIO11") (class "Default")
      (node (ref "J1") (pin "1") (pinfunction "P$1_1") (pintype "bidirectional"))
      (node (ref "X2") (pin "19") (pinfunction "CMD_19") (pintype "bidirectional"))
    )
    (net (code "13") (name "I2C_SCL5V") (class "Default")
      (node (ref "Q4") (pin "3") (pinfunction "D_3") (pintype "passive"))
      (node (ref "R29") (pin "1") (pinfunction "1_1") (pintype "passive"))
      (node (ref "U$59") (pin "10") (pinfunction "SCL_10") (pintype "bidirectional"))
    )
    (net (code "14") (name "I2C_SDA5V") (class "Default")
      (node (ref "Q3") (pin "3") (pinfunction "D_3") (pintype "passive"))
      (node (ref "R30") (pin "1") (pinfunction "1_1") (pintype "passive"))
      (node (ref "U$59") (pin "9") (pinfunction "SDA_9") (pintype "bidirectional"))
    )
    (net (code "15") (name "MICS_PREHEAT_NOX") (class "Default")
      (node (ref "Q1") (pin "1") (pinfunction "G_1") (pintype "passive"))
      (node (ref "X2") (pin "8") (pinfunction "IO32/A1_4/X32P_8") (pintype "bidirectional"))
    )
    (net (code "16") (name "MICS_PWR") (class "Default")
      (node (ref "Q5") (pin "1") (pinfunction "G_1") (pintype "passive"))
      (node (ref "X2") (pin "9") (pinfunction "IO33/A1_5/X32N_9") (pintype "bidirectional"))
    )
    (net (code "17") (name "Net-(1-Pad+)") (class "Default")
      (node (ref "1") (pin "+") (pinfunction "+_+") (pintype "passive"))
      (node (ref "R14") (pin "1") (pinfunction "1_1") (pintype "passive"))
    )
    (net (code "18") (name "Net-(2-Pad+)") (class "Default")
      (node (ref "2") (pin "+") (pinfunction "+_+") (pintype "passive"))
      (node (ref "R2") (pin "1") (pinfunction "1_1") (pintype "passive"))
    )
    (net (code "19") (name "Net-(3-Pad+)") (class "Default")
      (node (ref "3") (pin "+") (pinfunction "+_+") (pintype "passive"))
      (node (ref "R16") (pin "1") (pinfunction "1_1") (pintype "passive"))
    )
    (net (code "20") (name "Net-(4-Pad-)") (class "Default")
      (node (ref "4") (pin "-") (pinfunction "-_-") (pintype "passive"))
      (node (ref "R7") (pin "2") (pinfunction "2_2") (pintype "passive"))
    )
    (net (code "21") (name "Net-(ANT1-D)") (class "Default")
      (node (ref "ANT1") (pin "1") (pinfunction "D_1") (pintype "bidirectional"))
      (node (ref "C10") (pin "2") (pinfunction "2_2") (pintype "passive"))
      (node (ref "C9") (pin "2") (pinfunction "2_2") (pintype "passive"))
    )
    (net (code "22") (name "Net-(C5-Pad1)") (class "Default")
      (node (ref "C5") (pin "1") (pinfunction "1_1") (pintype "passive"))
      (node (ref "L2") (pin "P$2") (pinfunction "P$2_P$2") (pintype "passive"))
    )
    (net (code "23") (name "Net-(C11-Pad2)") (class "Default")
      (node (ref "C11") (pin "2") (pinfunction "2_2") (pintype "passive"))
      (node (ref "C5") (pin "2") (pinfunction "2_2") (pintype "passive"))
      (node (ref "C9") (pin "1") (pinfunction "1_1") (pintype "passive"))
    )
    (net (code "24") (name "Net-(Q1-D)") (class "Default")
      (node (ref "Q1") (pin "3") (pinfunction "D_3") (pintype "passive"))
      (node (ref "R23") (pin "1") (pinfunction "1_1") (pintype "passive"))
      (node (ref "R24") (pin "2") (pinfunction "2_2") (pintype "passive"))
    )
    (net (code "25") (name "Net-(Q5-S)") (class "Default")
      (node (ref "C26") (pin "2") (pinfunction "2_2") (pintype "passive"))
      (node (ref "Q5") (pin "2") (pinfunction "S_2") (pintype "passive"))
    )
    (net (code "26") (name "Net-(R20-Pad1)") (class "Default")
      (node (ref "R20") (pin "1") (pinfunction "1_1") (pintype "passive"))
      (node (ref "R25") (pin "2") (pinfunction "2_2") (pintype "passive"))
    )
    (net (code "27") (name "Net-(R22-Pad1)") (class "Default")
      (node (ref "R22") (pin "1") (pinfunction "1_1") (pintype "passive"))
      (node (ref "R26") (pin "2") (pinfunction "2_2") (pintype "passive"))
    )
    (net (code "28") (name "Net-(R37-Pad2)") (class "Default")
      (node (ref "R37") (pin "2") (pinfunction "2_2") (pintype "passive"))
      (node (ref "U$22") (pin "TXD") (pinfunction "TXD_TXD") (pintype "bidirectional"))
    )
    (net (code "29") (name "Net-(RELOAD-B1)") (class "Default")
      (node (ref "R13") (pin "1") (pinfunction "1_1") (pintype "passive"))
      (node (ref "RELOAD") (pin "3") (pinfunction "B1_3") (pintype "bidirectional"))
    )
    (net (code "30") (name "Net-(RESET-B1)") (class "Default")
      (node (ref "R4") (pin "1") (pinfunction "1_1") (pintype "passive"))
      (node (ref "RESET") (pin "3") (pinfunction "B1_3") (pintype "bidirectional"))
    )
    (net (code "31") (name "Net-(U$1-RH1_OX)") (class "Default")
      (node (ref "R23") (pin "2") (pinfunction "2_2") (pintype "passive"))
      (node (ref "U$1") (pin "A") (pinfunction "RH1_OX_A") (pintype "bidirectional"))
    )
    (net (code "32") (name "Net-(U$1-RH1_RED)") (class "Default")
      (node (ref "R21") (pin "2") (pinfunction "2_2") (pintype "passive"))
      (node (ref "U$1") (pin "C") (pinfunction "RH1_RED_C") (pintype "bidirectional"))
    )
    (net (code "33") (name "Net-(U$1-RH2_OX)") (class "Default")
      (node (ref "C26") (pin "1") (pinfunction "1_1") (pintype "passive"))
      (node (ref "U$1") (pin "F") (pinfunction "RH2_RED_F") (pintype "bidirectional"))
      (node (ref "U$1") (pin "G") (pinfunction "RS2_RED_G") (pintype "bidirectional"))
      (node (ref "U$1") (pin "H") (pinfunction "RH2_OX_H") (pintype "bidirectional"))
      (node (ref "U$1") (pin "J") (pinfunction "RS2_OX_J") (pintype "bidirectional"))
    )
    (net (code "34") (name "Net-(U$29-B)") (class "Default")
      (node (ref "R1") (pin "2") (pinfunction "2_2") (pintype "passive"))
      (node (ref "U$29") (pin "1") (pinfunction "B_1") (pintype "passive"))
    )
    (net (code "35") (name "Net-(U$34-B)") (class "Default")
      (node (ref "R3") (pin "2") (pinfunction "2_2") (pintype "passive"))
      (node (ref "U$34") (pin "1") (pinfunction "B_1") (pintype "passive"))
    )
    (net (code "36") (name "Net-(U2-TXD)") (class "Default")
      (node (ref "R34") (pin "2") (pinfunction "2_2") (pintype "passive"))
      (node (ref "U2") (pin "3") (pinfunction "TXD_3") (pintype "output"))
    )
    (net (code "37") (name "Net-(U2-UD+)") (class "Default")
      (node (ref "U2") (pin "6") (pinfunction "UD+_6") (pintype "bidirectional"))
      (node (ref "USB1") (pin "3") (pinfunction "D+_3") (pintype "bidirectional"))
    )
    (net (code "38") (name "Net-(U2-UD-)") (class "Default")
      (node (ref "U2") (pin "7") (pinfunction "UD-_7") (pintype "bidirectional"))
      (node (ref "USB1") (pin "2") (pinfunction "D-_2") (pintype "bidirectional"))
    )
    (net (code "39") (name "Net-(U2-XI)") (class "Default")
      (node (ref "C18") (pin "2") (pinfunction "2_2") (pintype "passive"))
      (node (ref "U2") (pin "9") (pinfunction "XI_9") (pintype "input"))
      (node (ref "Y1") (pin "2") (pinfunction "2_2") (pintype "passive"))
    )
    (net (code "40") (name "Net-(U2-XO)") (class "Default")
      (node (ref "C19") (pin "2") (pinfunction "2_2") (pintype "passive"))
      (node (ref "U2") (pin "10") (pinfunction "XO_10") (pintype "output"))
      (node (ref "Y1") (pin "1") (pinfunction "1_1") (pintype "passive"))
    )
    (net (code "41") (name "Net-(U4-RFIN)") (class "Default")
      (node (ref "L1") (pin "2") (pinfunction "2_2") (pintype "passive"))
      (node (ref "L2") (pin "P$1") (pinfunction "P$1_P$1") (pintype "passive"))
      (node (ref "U4") (pin "3") (pinfunction "RFIN_3") (pintype "bidirectional"))
    )
    (net (code "42") (name "Net-(U4-VCC)") (class "Default")
      (node (ref "C12") (pin "2") (pinfunction "2_2") (pintype "passive"))
      (node (ref "C15") (pin "2") (pinfunction "2_2") (pintype "passive"))
      (node (ref "R5") (pin "2") (pinfunction "2_2") (pintype "passive"))
      (node (ref "U4") (pin "4") (pinfunction "VCC_4") (pintype "power_in"))
    )
    (net (code "43") (name "Net-(U4-~{SHDN})") (class "Default")
      (node (ref "R6") (pin "2") (pinfunction "2_2") (pintype "passive"))
      (node (ref "U4") (pin "5") (pinfunction "~{SHDN}_5") (pintype "bidirectional"))
    )
    (net (code "44") (name "Net-(U5-RESERVED)") (class "Default")
      (node (ref "R18") (pin "2") (pinfunction "2_2") (pintype "passive"))
      (node (ref "U5") (pin "16") (pinfunction "RESERVED_16") (pintype "bidirectional"))
    )
    (net (code "45") (name "Net-(U5-RESERVED1)") (class "Default")
      (node (ref "R19") (pin "2") (pinfunction "2_2") (pintype "passive"))
      (node (ref "U5") (pin "17") (pinfunction "RESERVED1_17") (pintype "bidirectional"))
    )
    (net (code "46") (name "Net-(U5-TXD1)") (class "Default")
      (node (ref "R38") (pin "1") (pinfunction "1_1") (pintype "passive"))
      (node (ref "U5") (pin "2") (pinfunction "TXD1_2") (pintype "bidirectional"))
    )
    (net (code "47") (name "Net-(U5-V_BCKP)") (class "Default")
      (node (ref "BAT1") (pin "+1") (pinfunction "V+_+1") (pintype "bidirectional"))
      (node (ref "BAT1") (pin "+2") (pinfunction "V+_+2") (pintype "bidirectional"))
      (node (ref "U5") (pin "6") (pinfunction "V_BCKP_6") (pintype "bidirectional"))
    )
    (net (code "48") (name "Net-(USB1-VBUS)") (class "Default")
      (node (ref "L3") (pin "1") (pinfunction "1_1") (pintype "passive"))
      (node (ref "USB1") (pin "1") (pinfunction "VBUS_1") (pintype "power_in"))
    )
    (net (code "49") (name "Net-(X2-SD3)") (class "Default")
      (node (ref "R35") (pin "2") (pinfunction "2_2") (pintype "passive"))
      (node (ref "X2") (pin "18") (pinfunction "SD3_18") (pintype "bidirectional"))
    )
    (net (code "50") (name "Net-(X2-TXD0)") (class "Default")
      (node (ref "R33") (pin "2") (pinfunction "2_2") (pintype "passive"))
      (node (ref "X2") (pin "35") (pinfunction "TXD0_35") (pintype "output"))
    )
    (net (code "51") (name "PM_RESET") (class "Default")
      (node (ref "U$22") (pin "RESET") (pinfunction "RESET_RESET") (pintype "bidirectional"))
      (node (ref "X2") (pin "28") (pinfunction "IO17_28") (pintype "bidirectional"))
    )
    (net (code "52") (name "PM_SET") (class "Default")
      (node (ref "U$22") (pin "SET") (pinfunction "SET_SET") (pintype "bidirectional"))
      (node (ref "X2") (pin "29") (pinfunction "IO5_29") (pintype "bidirectional"))
    )
    (net (code "53") (name "RELOAD") (class "Default")
      (node (ref "C4") (pin "2") (pinfunction "2_2") (pintype "passive"))
      (node (ref "RELOAD") (pin "2") (pinfunction "B0_2") (pintype "bidirectional"))
      (node (ref "X2") (pin "4") (pinfunction "IO36/SEN_VP/A1_0_4") (pintype "passive"))
    )
    (net (code "54") (name "RESET") (class "Default")
      (node (ref "C3") (pin "2") (pinfunction "2_2") (pintype "passive"))
      (node (ref "RESET") (pin "2") (pinfunction "B0_2") (pintype "bidirectional"))
      (node (ref "U$34") (pin "2") (pinfunction "E_2") (pintype "passive"))
      (node (ref "X2") (pin "3") (pinfunction "EN_3") (pintype "input"))
    )
    (net (code "55") (name "RF_IN") (class "Default")
      (node (ref "U4") (pin "6") (pinfunction "RFOUT_6") (pintype "bidirectional"))
      (node (ref "U5") (pin "11") (pinfunction "RF_IN_11") (pintype "bidirectional"))
    )
    (net (code "56") (name "RTS") (class "Default")
      (node (ref "R1") (pin "1") (pinfunction "1_1") (pintype "passive"))
      (node (ref "U$34") (pin "3") (pinfunction "C_3") (pintype "passive"))
      (node (ref "U2") (pin "16") (pinfunction "RTS#_16") (pintype "output"))
    )
    (net (code "57") (name "RXD0") (class "Default")
      (node (ref "R34") (pin "1") (pinfunction "1_1") (pintype "passive"))
      (node (ref "X2") (pin "34") (pinfunction "RXD0_34") (pintype "input"))
    )
    (net (code "58") (name "SCL") (class "Default")
      (node (ref "Q4") (pin "2") (pinfunction "S_2") (pintype "passive"))
      (node (ref "R27") (pin "1") (pinfunction "1_1") (pintype "passive"))
      (node (ref "U1") (pin "6") (pinfunction "SCL_6") (pintype "input"))
      (node (ref "X2") (pin "12") (pinfunction "IO27/A2_7_12") (pintype "bidirectional"))
    )
    (net (code "59") (name "SDA") (class "Default")
      (node (ref "Q3") (pin "2") (pinfunction "S_2") (pintype "passive"))
      (node (ref "R31") (pin "1") (pinfunction "1_1") (pintype "passive"))
      (node (ref "U1") (pin "1") (pinfunction "SDA_1") (pintype "bidirectional"))
      (node (ref "X2") (pin "11") (pinfunction "IO26/DAC2/A2_9_11") (pintype "bidirectional"))
    )
    (net (code "60") (name "SD_CLK_IO14") (class "Default")
      (node (ref "R15") (pin "1") (pinfunction "1_1") (pintype "passive"))
      (node (ref "SD1") (pin "5") (pinfunction "SCLK_5") (pintype "bidirectional"))
      (node (ref "X2") (pin "13") (pinfunction "IO14/A2_6_13") (pintype "bidirectional"))
    )
    (net (code "61") (name "SD_CMD_IO15") (class "Default")
      (node (ref "R17") (pin "1") (pinfunction "1_1") (pintype "passive"))
      (node (ref "SD1") (pin "3") (pinfunction "DI_3") (pintype "bidirectional"))
      (node (ref "X2") (pin "23") (pinfunction "IO15/A2_3_23") (pintype "bidirectional"))
    )
    (net (code "62") (name "SD_CS_IO13") (class "Default")
      (node (ref "R8") (pin "1") (pinfunction "1_1") (pintype "passive"))
      (node (ref "SD1") (pin "2") (pinfunction "CS_2") (pintype "bidirectional"))
      (node (ref "X2") (pin "16") (pinfunction "IO13/A2_4_16") (pintype "bidirectional"))
    )
    (net (code "63") (name "SD_D0_IO2") (class "Default")
      (node (ref "R12") (pin "2") (pinfunction "2_2") (pintype "passive"))
      (node (ref "R9") (pin "1") (pinfunction "1_1") (pintype "passive"))
      (node (ref "SD1") (pin "7") (pinfunction "DO_7") (pintype "bidirectional"))
      (node (ref "X2") (pin "24") (pinfunction "IO2/A2_2_24") (pintype "bidirectional"))
    )
    (net (code "64") (name "SD_D1_IO4") (class "Default")
      (node (ref "SD1") (pin "8") (pinfunction "DATA1_8") (pintype "bidirectional"))
      (node (ref "X2") (pin "26") (pinfunction "IO4/A2_0_26") (pintype "bidirectional"))
    )
    (net (code "65") (name "SD_D2_IO12") (class "Default")
      (node (ref "SD1") (pin "1") (pinfunction "DATA2_1") (pintype "bidirectional"))
      (node (ref "X2") (pin "14") (pinfunction "IO12/A2_5_14") (pintype "bidirectional"))
    )
    (net (code "66") (name "STANDBY") (class "Default")
      (node (ref "U5") (pin "5") (pinfunction "STANDBY_5") (pintype "bidirectional"))
      (node (ref "X2") (pin "36") (pinfunction "IO22_36") (pintype "bidirectional"))
    )
    (net (code "67") (name "STAT_LED1") (class "Default")
      (node (ref "R14") (pin "2") (pinfunction "2_2") (pintype "passive"))
      (node (ref "X2") (pin "33") (pinfunction "IO21_33") (pintype "bidirectional"))
    )
    (net (code "68") (name "STAT_LED2") (class "Default")
      (node (ref "R2") (pin "2") (pinfunction "2_2") (pintype "passive"))
      (node (ref "X2") (pin "31") (pinfunction "IO19_31") (pintype "bidirectional"))
    )
    (net (code "69") (name "STAT_LED3") (class "Default")
      (node (ref "R16") (pin "2") (pinfunction "2_2") (pintype "passive"))
      (node (ref "X2") (pin "30") (pinfunction "IO18_30") (pintype "bidirectional"))
    )
    (net (code "70") (name "TIMER") (class "Default")
      (node (ref "U5") (pin "18") (pinfunction "TIMER_18") (pintype "bidirectional"))
      (node (ref "X2") (pin "37") (pinfunction "IO23_37") (pintype "bidirectional"))
    )
    (net (code "71") (name "TXD0") (class "Default")
      (node (ref "R33") (pin "1") (pinfunction "1_1") (pintype "passive"))
      (node (ref "U2") (pin "4") (pinfunction "RXD_4") (pintype "input"))
    )
    (net (code "72") (name "U1RXD") (class "Default")
      (node (ref "R38") (pin "2") (pinfunction "2_2") (pintype "passive"))
      (node (ref "X2") (pin "17") (pinfunction "SD2_17") (pintype "bidirectional"))
    )
    (net (code "73") (name "U1TXD") (class "Default")
      (node (ref "R35") (pin "1") (pinfunction "1_1") (pintype "passive"))
      (node (ref "U5") (pin "3") (pinfunction "RXD1_3") (pintype "bidirectional"))
    )
    (net (code "74") (name "U2RXD") (class "Default")
      (node (ref "R37") (pin "1") (pinfunction "1_1") (pintype "passive"))
      (node (ref "X2") (pin "27") (pinfunction "IO16_27") (pintype "bidirectional"))
    )
    (net (code "75") (name "VCC_RF") (class "Default")
      (node (ref "R5") (pin "1") (pinfunction "1_1") (pintype "passive"))
      (node (ref "U5") (pin "14") (pinfunction "VCC_RF_14") (pintype "power_in"))
    )
    (net (code "76") (name "VOX_RAWA") (class "Default")
      (node (ref "R22") (pin "2") (pinfunction "2_2") (pintype "passive"))
      (node (ref "U$1") (pin "B") (pinfunction "RS1_OX_B") (pintype "bidirectional"))
      (node (ref "U$74") (pin "3") (pinfunction "3_3") (pintype "bidirectional"))
    )
    (net (code "77") (name "VOX_RAWB") (class "Default")
      (node (ref "U$59") (pin "4") (pinfunction "AIN0_4") (pintype "input"))
      (node (ref "U$74") (pin "1") (pinfunction "1_1") (pintype "bidirectional"))
      (node (ref "U$74") (pin "2") (pinfunction "2_2") (pintype "bidirectional"))
    )
    (net (code "78") (name "VRED_RAWA") (class "Default")
      (node (ref "R20") (pin "2") (pinfunction "2_2") (pintype "passive"))
      (node (ref "U$1") (pin "D") (pinfunction "RS1_RED_D") (pintype "bidirectional"))
      (node (ref "U$74") (pin "5") (pinfunction "5_5") (pintype "bidirectional"))
    )
    (net (code "79") (name "VRED_RAWB") (class "Default")
      (node (ref "U$59") (pin "5") (pinfunction "AIN1_5") (pintype "input"))
      (node (ref "U$74") (pin "6") (pinfunction "6_6") (pintype "bidirectional"))
      (node (ref "U$74") (pin "7") (pinfunction "7_7") (pintype "bidirectional"))
    )
    (net (code "80") (name "unconnected-(SD1-CDN-Pad9)") (class "Default")
      (node (ref "SD1") (pin "9") (pinfunction "CDN_9") (pintype "bidirectional"))
    )
    (net (code "81") (name "unconnected-(U$22-PadRXD)") (class "Default")
      (node (ref "U$22") (pin "RXD") (pinfunction "RXD_RXD") (pintype "bidirectional"))
    )
    (net (code "82") (name "unconnected-(U$59-AIN2-Pad6)") (class "Default")
      (node (ref "U$59") (pin "6") (pinfunction "AIN2_6") (pintype "input"))
    )
    (net (code "83") (name "unconnected-(U$59-AIN3-Pad7)") (class "Default")
      (node (ref "U$59") (pin "7") (pinfunction "AIN3_7") (pintype "input"))
    )
    (net (code "84") (name "unconnected-(U2-ACT#-Pad2)") (class "Default")
      (node (ref "U2") (pin "2") (pinfunction "ACT#_2") (pintype "output"))
    )
    (net (code "85") (name "unconnected-(U2-CKO-Pad1)") (class "Default")
      (node (ref "U2") (pin "1") (pinfunction "CKO_1") (pintype "output"))
    )
    (net (code "86") (name "unconnected-(U2-CTS#-Pad11)") (class "Default")
      (node (ref "U2") (pin "11") (pinfunction "CTS#_11") (pintype "input"))
    )
    (net (code "87") (name "unconnected-(U2-DCD#-Pad14)") (class "Default")
      (node (ref "U2") (pin "14") (pinfunction "DCD#_14") (pintype "input"))
    )
    (net (code "88") (name "unconnected-(U2-DSR#-Pad12)") (class "Default")
      (node (ref "U2") (pin "12") (pinfunction "DSR#_12") (pintype "input"))
    )
    (net (code "89") (name "unconnected-(U2-NC-Pad17)") (class "Default")
      (node (ref "U2") (pin "17") (pinfunction "NC_17") (pintype "no_connect"))
    )
    (net (code "90") (name "unconnected-(U2-R232-Pad18)") (class "Default")
      (node (ref "U2") (pin "18") (pinfunction "R232_18") (pintype "input"))
    )
    (net (code "91") (name "unconnected-(U2-RI#-Pad13)") (class "Default")
      (node (ref "U2") (pin "13") (pinfunction "RI#_13") (pintype "input"))
    )
    (net (code "92") (name "unconnected-(U5-NC-Pad7)") (class "Default")
      (node (ref "U5") (pin "7") (pinfunction "NC_7") (pintype "bidirectional"))
    )
    (net (code "93") (name "unconnected-(U5-NC-Pad15)") (class "Default")
      (node (ref "U5") (pin "15") (pinfunction "NC_15") (pintype "bidirectional"))
    )
    (net (code "94") (name "unconnected-(USB1-ID-Pad4)") (class "Default")
      (node (ref "USB1") (pin "4") (pinfunction "ID_4") (pintype "bidirectional"))
    )
    (net (code "95") (name "unconnected-(X2-IO25{slash}DAC1{slash}A2_8-Pad10)") (class "Default")
      (node (ref "X2") (pin "10") (pinfunction "IO25/DAC1/A2_8_10") (pintype "bidirectional"))
    )
    (net (code "96") (name "unconnected-(X2-IO39{slash}SEN_VN{slash}A1_3-Pad5)") (class "Default")
      (node (ref "X2") (pin "5") (pinfunction "IO39/SEN_VN/A1_3_5") (pintype "passive"))
    )
  )
)
